# 2V_AUX.net
KiCad netlist of a schematic drawn in Altium Designer
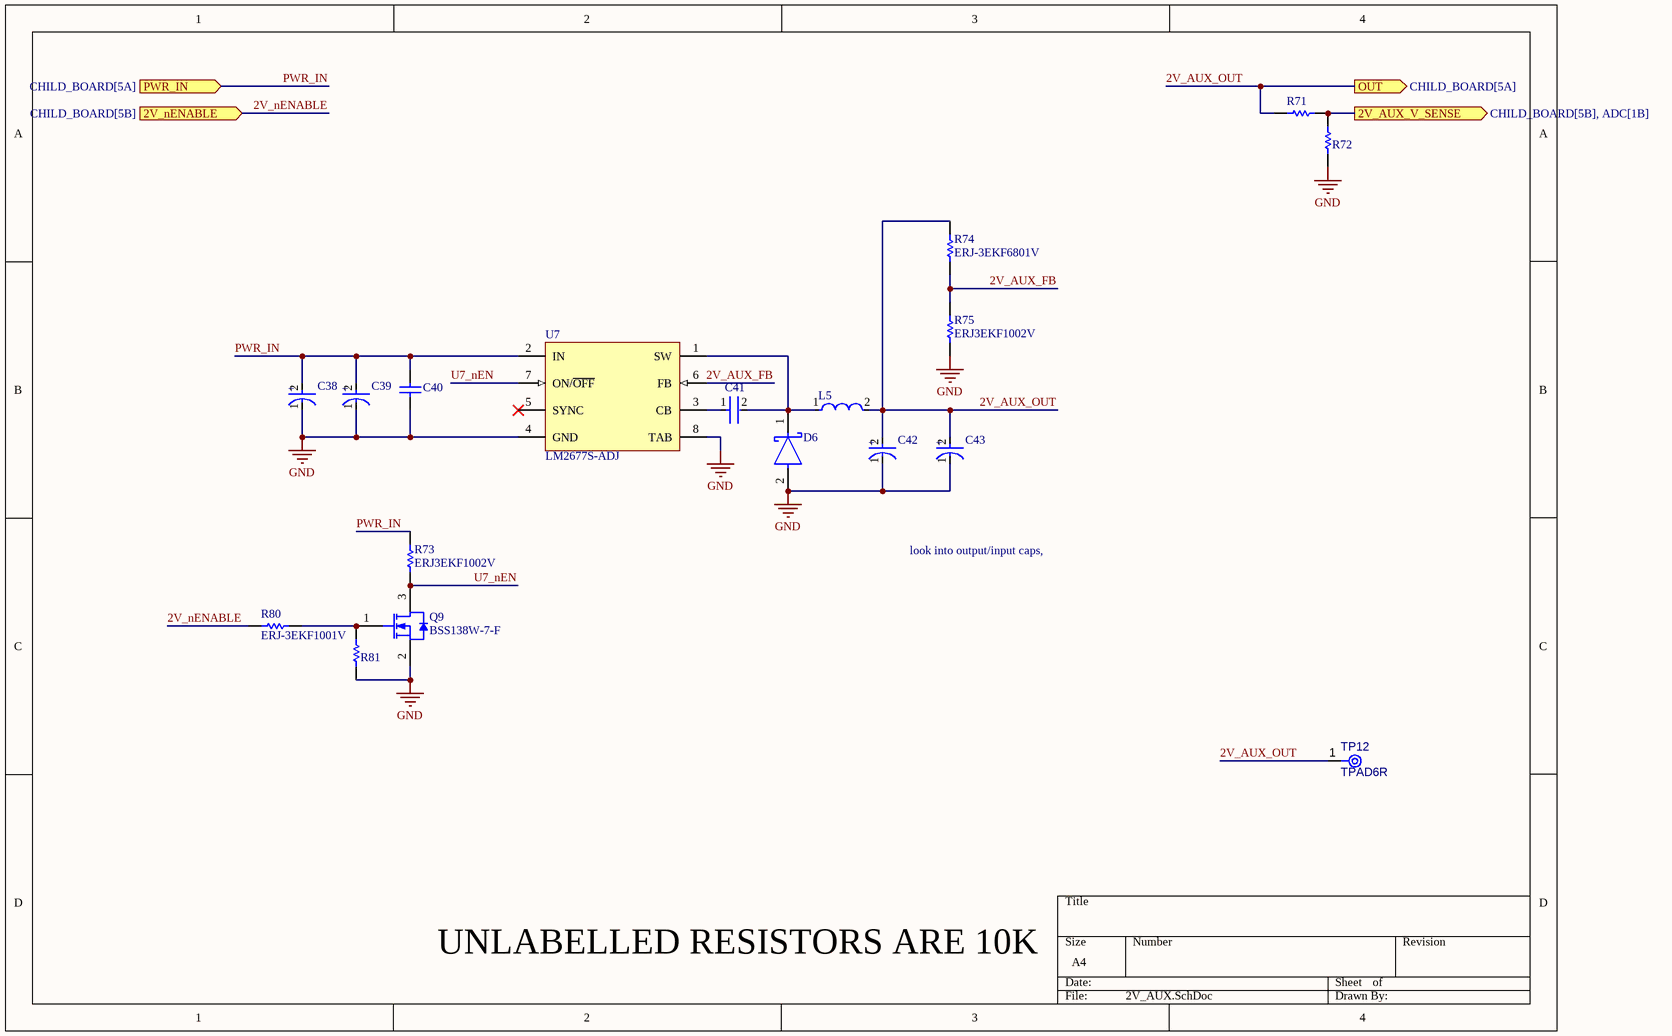
[diagram p0: 2V_AUX.SchDoc]

(export (version "E")
  (design (tool "Eeschema 10.0.6"))
  (components
    (comp (ref "C38")
      (value "EEHZA1V680XP")
      (footprint "FP-EEH-D8-MFG")
      (description "Conductive Polymer Hybrid Aluminum Electrolytic Capacitors 68uF ±20% 35V RADIAL SMT 6.3x7.7mm")
      (fields (field (name "VOLTAGE") "35V") (field (name "TOLERANCE") "20%"))
      (libsource (lib "Altium Content Vault") (part "a00bbbee19879c290e62620ae7e47b1"))
    )
    (comp (ref "C39")
      (value "EEHZA1V680XP")
      (footprint "FP-EEH-D8-MFG")
      (description "Conductive Polymer Hybrid Aluminum Electrolytic Capacitors 68uF ±20% 35V RADIAL SMT 6.3x7.7mm")
      (fields (field (name "VOLTAGE") "35V") (field (name "TOLERANCE") "20%"))
      (libsource (lib "Altium Content Vault") (part "a00bbbee19879c290e62620ae7e47b1"))
    )
    (comp (ref "C40")
      (value "CAP 470nF 50V 1812(4532)")
      (footprint "CAPC1812(4532)125_M")
      (description "CAP 470nF 50V ±10% 1812 (4532 Metric) Thickness 1.25mm SMD")
      (fields (field (name "TOLERANCE") "Â±10%"))
      (libsource (lib "Altium Content Vault") (part "CAP"))
    )
    (comp (ref "C41")
      (value "C0805C103J5RACTU")
      (footprint "FP-C0805C-DN-MFG")
      (description "CAP CER 10000PF 50V X7R 0805")
      (fields
        (field (name "MANUFACTURER") "KEMET")
        (field (name "OCTOPART") "https://octopart.com/c0805c103j5ractu-kemet-133473")
      )
      (libsource (lib "Altium Content Vault") (part "b4654b650e69147ec39a6b967a45e02"))
    )
    (comp (ref "C42")
      (value "16SVPC120M")
      (footprint "FP-OS-CON-SMT-E7-MFG")
      (description "Conductive Polymer Aluminum Solid Capacitors (OS-CON) 120uF ±20% 16V RADIAL SMT 8x6.9mm")
      (fields (field (name "VOLTAGE") "16V") (field (name "TOLERANCE") "20%"))
      (libsource (lib "Altium Content Vault") (part "cf48714ba7e38822c1575c7ec0b6d1f"))
    )
    (comp (ref "C43")
      (value "16SVPC120M")
      (footprint "FP-OS-CON-SMT-E7-MFG")
      (description "Conductive Polymer Aluminum Solid Capacitors (OS-CON) 120uF ±20% 16V RADIAL SMT 8x6.9mm")
      (fields (field (name "VOLTAGE") "16V") (field (name "TOLERANCE") "20%"))
      (libsource (lib "Altium Content Vault") (part "cf48714ba7e38822c1575c7ec0b6d1f"))
    )
    (comp (ref "D6")
      (value "B540C-13-F")
      (footprint "FP-SMC-MFG")
      (description "DIODE SCHOTTKY 40V 5A SMC")
      (fields
        (field (name "OCTOPART") "https://octopart.com/b540c-13-f-diodes+inc.-325873")
        (field (name "MANUFACTURER") "Diodes Inc.")
      )
      (libsource (lib "Altium Content Vault") (part "1d6ec82d83fb6aee721767c19dac4b9"))
    )
    (comp (ref "L5")
      (value "SRR1260-150M")
      (footprint "FP-SRR1260-MFG")
      (description "FIXED IND 15UH 5A 27 MOHM SMD")
      (fields (field (name "TOLERANCE") "20%"))
      (libsource (lib "Altium Content Vault") (part "725321dda6339637d4d059423bc1c3c"))
    )
    (comp (ref "Q9")
      (value "BSS138W-7-F")
      (footprint "DIOD-SOT323-3_V")
      (fields (field (name "MANUFACTURER") "DiodesIncorporated"))
      (libsource (lib "Altium Content Vault") (part "NEMOS-GSD-3"))
    )
    (comp (ref "R71")
      (value "ERJ3EKF1002V")
      (footprint "RESC1609X55X30LL15T15")
      (description "Chip Resistor, 10 KOhm, +/- 1%, 0.1 W, -55 to 155 degC, 0603 (1608 Metric), RoHS, Tape and Reel")
      (fields (field (name "TOLERANCE") "1%") (field (name "MANUFACTURER") "Panasonic"))
      (libsource (lib "Altium Content Vault") (part "RES-2"))
    )
    (comp (ref "R72")
      (value "ERJ3EKF1002V")
      (footprint "RESC1609X55X30LL15T15")
      (description "Chip Resistor, 10 KOhm, +/- 1%, 0.1 W, -55 to 155 degC, 0603 (1608 Metric), RoHS, Tape and Reel")
      (fields (field (name "TOLERANCE") "1%") (field (name "MANUFACTURER") "Panasonic"))
      (libsource (lib "Altium Content Vault") (part "RES-2"))
    )
    (comp (ref "R73")
      (value "ERJ3EKF1002V")
      (footprint "RESC1609X55X30LL15T15")
      (description "Chip Resistor, 10 KOhm, +/- 1%, 0.1 W, -55 to 155 degC, 0603 (1608 Metric), RoHS, Tape and Reel")
      (fields (field (name "TOLERANCE") "1%") (field (name "MANUFACTURER") "Panasonic"))
      (libsource (lib "Altium Content Vault") (part "RES-2"))
    )
    (comp (ref "R74")
      (value "ERJ-3EKF6801V")
      (footprint "RESC1609X55X30NL15T15")
      (description "Chip Resistor, 6.8 KOhm, +/- 1%, 0.1 W, -55 to 155 degC, 0603 (1608 Metric), RoHS, Tape and Reel")
      (libsource (lib "Altium Content Vault") (part "RES-2"))
    )
    (comp (ref "R75")
      (value "ERJ3EKF1002V")
      (footprint "RESC1609X55X30LL15T15")
      (description "Chip Resistor, 10 KOhm, +/- 1%, 0.1 W, -55 to 155 degC, 0603 (1608 Metric), RoHS, Tape and Reel")
      (fields (field (name "TOLERANCE") "1%") (field (name "MANUFACTURER") "Panasonic"))
      (libsource (lib "Altium Content Vault") (part "RES-2"))
    )
    (comp (ref "R80")
      (value "ERJ-3EKF1001V")
      (footprint "RESC1608X55X30LL15T15")
      (fields (field (name "MANUFACTURER") "Panasonic"))
      (libsource (lib "Altium Content Vault") (part "RES"))
    )
    (comp (ref "R81")
      (value "ERJ3EKF1002V")
      (footprint "RESC1609X55X30LL15T15")
      (description "Chip Resistor, 10 KOhm, +/- 1%, 0.1 W, -55 to 155 degC, 0603 (1608 Metric), RoHS, Tape and Reel")
      (fields (field (name "TOLERANCE") "1%") (field (name "MANUFACTURER") "Panasonic"))
      (libsource (lib "Altium Content Vault") (part "RES-2"))
    )
    (comp (ref "TP12")
      (value "TPAD6R")
      (footprint "TP06R")
      (description "0.6mm round")
      (libsource (lib "uORocketry Hardware") (part "CMP-001-0001-4"))
    )
    (comp (ref "U7")
      (value "LM2677S-ADJ")
      (footprint "KTW0007B_M")
      (description "SIMPLE SWITCHER® High Efficiency 5A Step-Down Voltage Regulator with Sync, 7-pin TO-263")
      (fields (field (name "MANUFACTURER") "Texas Instruments"))
      (libsource (lib "Altium Content Vault") (part "PM-REG-LM2670S-12"))
    )
  )
  (nets
    (net (code "1") (name "/2V_AUX_FB") (class "Default")
      (node (ref "R74") (pin "1") (pinfunction "1_1") (pintype "passive"))
      (node (ref "R75") (pin "2") (pinfunction "2_2") (pintype "passive"))
      (node (ref "U7") (pin "6") (pinfunction "FB_6") (pintype "input"))
    )
    (net (code "2") (name "/2V_AUX_OUT") (class "Default")
      (node (ref "C42") (pin "2") (pinfunction "A_2") (pintype "passive"))
      (node (ref "C43") (pin "2") (pinfunction "A_2") (pintype "passive"))
      (node (ref "L5") (pin "2") (pinfunction "2_2") (pintype "passive"))
      (node (ref "R71") (pin "1") (pinfunction "1_1") (pintype "passive"))
      (node (ref "R74") (pin "2") (pinfunction "2_2") (pintype "passive"))
      (node (ref "TP12") (pin "1") (pinfunction "TP_1") (pintype "passive"))
    )
    (net (code "3") (name "/2V_AUX_V_SENSE") (class "Default")
      (node (ref "R71") (pin "2") (pinfunction "2_2") (pintype "passive"))
      (node (ref "R72") (pin "2") (pinfunction "2_2") (pintype "passive"))
    )
    (net (code "4") (name "/2V_nENABLE") (class "Default")
      (node (ref "R80") (pin "1") (pinfunction "1_1") (pintype "passive"))
    )
    (net (code "5") (name "/PWR_IN") (class "Default")
      (node (ref "C38") (pin "2") (pinfunction "A_2") (pintype "passive"))
      (node (ref "C39") (pin "2") (pinfunction "A_2") (pintype "passive"))
      (node (ref "C40") (pin "2") (pinfunction "2_2") (pintype "passive"))
      (node (ref "R73") (pin "2") (pinfunction "2_2") (pintype "passive"))
      (node (ref "U7") (pin "2") (pinfunction "IN_2") (pintype "power_in"))
    )
    (net (code "6") (name "/U7_nEN") (class "Default")
      (node (ref "Q9") (pin "3") (pinfunction "D_3") (pintype "passive"))
      (node (ref "R73") (pin "1") (pinfunction "1_1") (pintype "passive"))
      (node (ref "U7") (pin "7") (pinfunction "ON/~{OFF}_7") (pintype "input"))
    )
    (net (code "7") (name "GND") (class "Default")
      (node (ref "C38") (pin "1") (pinfunction "C_1") (pintype "passive"))
      (node (ref "C39") (pin "1") (pinfunction "C_1") (pintype "passive"))
      (node (ref "C40") (pin "1") (pinfunction "1_1") (pintype "passive"))
      (node (ref "C42") (pin "1") (pinfunction "C_1") (pintype "passive"))
      (node (ref "C43") (pin "1") (pinfunction "C_1") (pintype "passive"))
      (node (ref "D6") (pin "2") (pinfunction "A_2") (pintype "passive"))
      (node (ref "Q9") (pin "2") (pinfunction "S_2") (pintype "passive"))
      (node (ref "R72") (pin "1") (pinfunction "1_1") (pintype "passive"))
      (node (ref "R75") (pin "1") (pinfunction "1_1") (pintype "passive"))
      (node (ref "R81") (pin "1") (pinfunction "1_1") (pintype "passive"))
      (node (ref "U7") (pin "4") (pinfunction "GND_4") (pintype "power_in"))
      (node (ref "U7") (pin "8") (pinfunction "TAB_8") (pintype "passive"))
    )
    (net (code "8") (name "Net-(D6-C)") (class "Default")
      (node (ref "C41") (pin "2") (pinfunction "2_2") (pintype "passive"))
      (node (ref "D6") (pin "1") (pinfunction "C_1") (pintype "passive"))
      (node (ref "L5") (pin "1") (pinfunction "1_1") (pintype "passive"))
      (node (ref "U7") (pin "1") (pinfunction "SW_1") (pintype "power_in"))
    )
    (net (code "9") (name "Net-(Q9-G)") (class "Default")
      (node (ref "Q9") (pin "1") (pinfunction "G_1") (pintype "passive"))
      (node (ref "R80") (pin "2") (pinfunction "2_2") (pintype "passive"))
      (node (ref "R81") (pin "2") (pinfunction "2_2") (pintype "passive"))
    )
    (net (code "10") (name "Net-(U7-CB)") (class "Default")
      (node (ref "C41") (pin "1") (pinfunction "1_1") (pintype "passive"))
      (node (ref "U7") (pin "3") (pinfunction "CB_3") (pintype "passive"))
    )
    (net (code "11") (name "unconnected-(U7-SYNC-Pad5)") (class "Default")
      (node (ref "U7") (pin "5") (pinfunction "SYNC_5") (pintype "passive+no_connect"))
    )
  )
)
